# SparkFun_ESP32_Power_Control_Shield.net
KiCad netlist of a schematic drawn in EAGLE
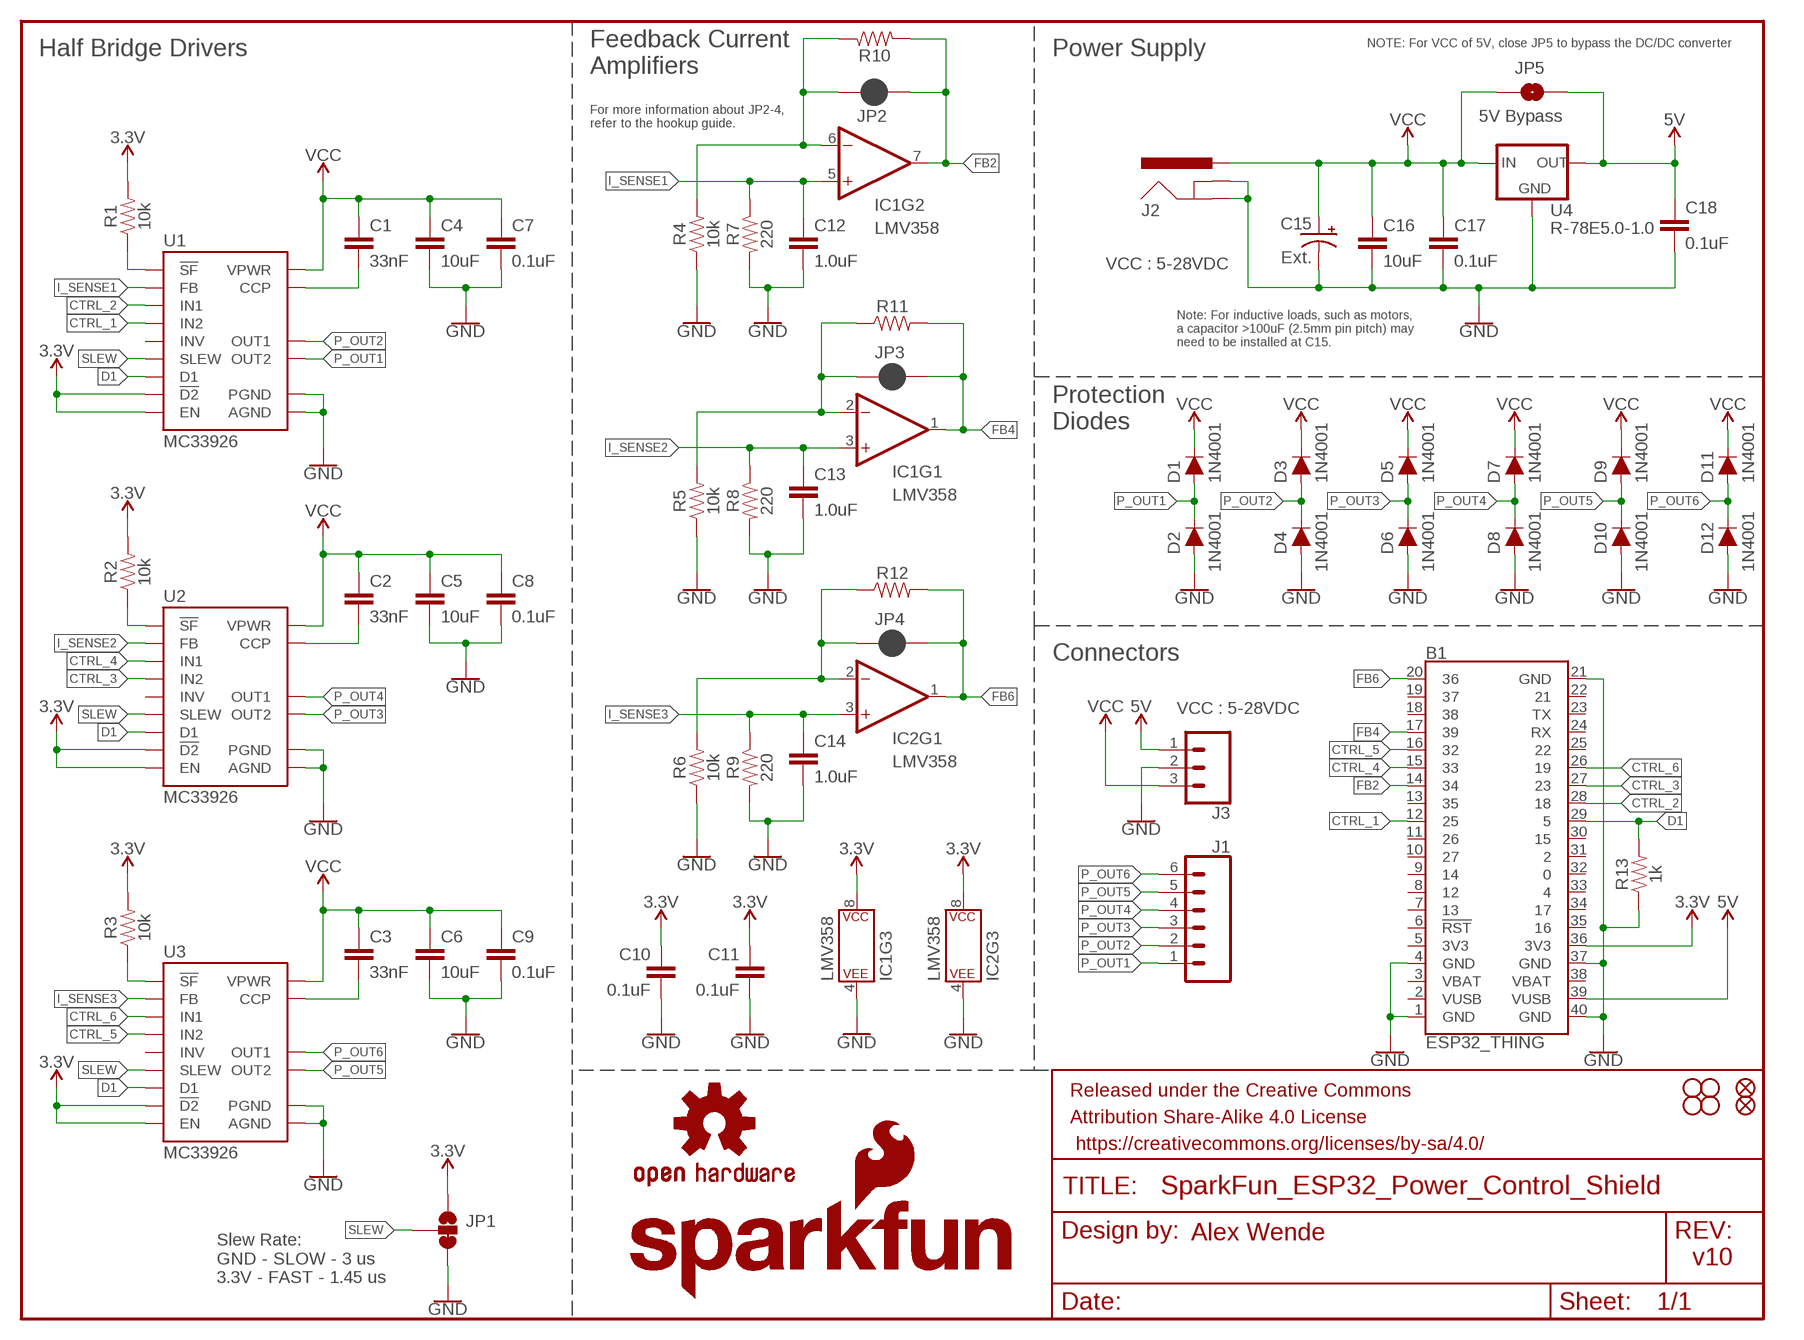
[diagram p0: schematic, sheet 1]

(export (version "E")
  (design (tool "Eeschema 10.0.6"))
  (components
    (comp (ref "B1")
      (value "ESP32_THING")
      (footprint "eagle-import:ESP32_THING")
      (libsource (lib "eagle-import") (part "ESP32_THING"))
    )
    (comp (ref "C1")
      (value "33nF")
      (footprint "eagle-import:0603")
      (libsource (lib "eagle-import") (part "33NF-0603-50V-10%"))
    )
    (comp (ref "C2")
      (value "33nF")
      (footprint "eagle-import:0603")
      (libsource (lib "eagle-import") (part "33NF-0603-50V-10%"))
    )
    (comp (ref "C3")
      (value "33nF")
      (footprint "eagle-import:0603")
      (libsource (lib "eagle-import") (part "33NF-0603-50V-10%"))
    )
    (comp (ref "C4")
      (value "10uF")
      (footprint "eagle-import:1210")
      (libsource (lib "eagle-import") (part "10UF-1210-50V-20%"))
    )
    (comp (ref "C5")
      (value "10uF")
      (footprint "eagle-import:1210")
      (libsource (lib "eagle-import") (part "10UF-1210-50V-20%"))
    )
    (comp (ref "C6")
      (value "10uF")
      (footprint "eagle-import:1210")
      (libsource (lib "eagle-import") (part "10UF-1210-50V-20%"))
    )
    (comp (ref "C7")
      (value "0.1uF")
      (footprint "eagle-import:0603")
      (libsource (lib "eagle-import") (part "0.1UF-0603-100V-10%"))
    )
    (comp (ref "C8")
      (value "0.1uF")
      (footprint "eagle-import:0603")
      (libsource (lib "eagle-import") (part "0.1UF-0603-100V-10%"))
    )
    (comp (ref "C9")
      (value "0.1uF")
      (footprint "eagle-import:0603")
      (libsource (lib "eagle-import") (part "0.1UF-0603-100V-10%"))
    )
    (comp (ref "C10")
      (value "0.1uF")
      (footprint "eagle-import:0603")
      (libsource (lib "eagle-import") (part "0.1UF-0603-100V-10%"))
    )
    (comp (ref "C11")
      (value "0.1uF")
      (footprint "eagle-import:0603")
      (libsource (lib "eagle-import") (part "0.1UF-0603-100V-10%"))
    )
    (comp (ref "C12")
      (value "1.0uF")
      (footprint "eagle-import:0603")
      (libsource (lib "eagle-import") (part "1.0UF-0603-16V-10%"))
    )
    (comp (ref "C13")
      (value "1.0uF")
      (footprint "eagle-import:0603")
      (libsource (lib "eagle-import") (part "1.0UF-0603-16V-10%"))
    )
    (comp (ref "C14")
      (value "1.0uF")
      (footprint "eagle-import:0603")
      (libsource (lib "eagle-import") (part "1.0UF-0603-16V-10%"))
    )
    (comp (ref "C15")
      (value "Ext.")
      (footprint "eagle-import:CPOL-RADIAL-2.5MM-6.5MM")
      (libsource (lib "eagle-import") (part "100UF-POLAR-RADIAL-2.5MM-25V-20%"))
    )
    (comp (ref "C16")
      (value "10uF")
      (footprint "eagle-import:1210")
      (libsource (lib "eagle-import") (part "10UF-1210-50V-20%"))
    )
    (comp (ref "C17")
      (value "0.1uF")
      (footprint "eagle-import:0603")
      (libsource (lib "eagle-import") (part "0.1UF-0603-100V-10%"))
    )
    (comp (ref "C18")
      (value "0.1uF")
      (footprint "eagle-import:0603")
      (libsource (lib "eagle-import") (part "0.1UF-0603-100V-10%"))
    )
    (comp (ref "D1")
      (value "1N4001")
      (footprint "eagle-import:DIODE-1N4001")
      (libsource (lib "eagle-import") (part "DIODE-PTH"))
    )
    (comp (ref "D2")
      (value "1N4001")
      (footprint "eagle-import:DIODE-1N4001")
      (libsource (lib "eagle-import") (part "DIODE-PTH"))
    )
    (comp (ref "D3")
      (value "1N4001")
      (footprint "eagle-import:DIODE-1N4001")
      (libsource (lib "eagle-import") (part "DIODE-PTH"))
    )
    (comp (ref "D4")
      (value "1N4001")
      (footprint "eagle-import:DIODE-1N4001")
      (libsource (lib "eagle-import") (part "DIODE-PTH"))
    )
    (comp (ref "D5")
      (value "1N4001")
      (footprint "eagle-import:DIODE-1N4001")
      (libsource (lib "eagle-import") (part "DIODE-PTH"))
    )
    (comp (ref "D6")
      (value "1N4001")
      (footprint "eagle-import:DIODE-1N4001")
      (libsource (lib "eagle-import") (part "DIODE-PTH"))
    )
    (comp (ref "D7")
      (value "1N4001")
      (footprint "eagle-import:DIODE-1N4001")
      (libsource (lib "eagle-import") (part "DIODE-PTH"))
    )
    (comp (ref "D8")
      (value "1N4001")
      (footprint "eagle-import:DIODE-1N4001")
      (libsource (lib "eagle-import") (part "DIODE-PTH"))
    )
    (comp (ref "D9")
      (value "1N4001")
      (footprint "eagle-import:DIODE-1N4001")
      (libsource (lib "eagle-import") (part "DIODE-PTH"))
    )
    (comp (ref "D10")
      (value "1N4001")
      (footprint "eagle-import:DIODE-1N4001")
      (libsource (lib "eagle-import") (part "DIODE-PTH"))
    )
    (comp (ref "D11")
      (value "1N4001")
      (footprint "eagle-import:DIODE-1N4001")
      (libsource (lib "eagle-import") (part "DIODE-PTH"))
    )
    (comp (ref "D12")
      (value "1N4001")
      (footprint "eagle-import:DIODE-1N4001")
      (libsource (lib "eagle-import") (part "DIODE-PTH"))
    )
    (comp (ref "FD1")
      (value "FIDUCIALUFIDUCIAL")
      (footprint "eagle-import:FIDUCIAL-MICRO")
      (libsource (lib "eagle-import") (part "FIDUCIALUFIDUCIAL"))
    )
    (comp (ref "FD2")
      (value "FIDUCIALUFIDUCIAL")
      (footprint "eagle-import:FIDUCIAL-MICRO")
      (libsource (lib "eagle-import") (part "FIDUCIALUFIDUCIAL"))
    )
    (comp (ref "FRAME1")
      (value "FRAME-LETTER")
      (footprint "eagle-import:CREATIVE_COMMONS")
      (libsource (lib "eagle-import") (part "FRAME-LETTER"))
    )
    (comp (ref "H1")
      (value "STAND-OFF")
      (footprint "eagle-import:STAND-OFF")
      (libsource (lib "eagle-import") (part "STAND-OFF"))
    )
    (comp (ref "H2")
      (value "STAND-OFF")
      (footprint "eagle-import:STAND-OFF")
      (libsource (lib "eagle-import") (part "STAND-OFF"))
    )
    (comp (ref "H3")
      (value "STAND-OFF")
      (footprint "eagle-import:STAND-OFF")
      (libsource (lib "eagle-import") (part "STAND-OFF"))
    )
    (comp (ref "H4")
      (value "STAND-OFF")
      (footprint "eagle-import:STAND-OFF")
      (libsource (lib "eagle-import") (part "STAND-OFF"))
    )
    (comp (ref "IC1")
      (value "LMV358")
      (footprint "eagle-import:SO08")
      (libsource (lib "eagle-import") (part "OPAMP-DUALU"))
    )
    (comp (ref "IC2")
      (value "LMV358")
      (footprint "eagle-import:SO08")
      (libsource (lib "eagle-import") (part "OPAMP-DUALU"))
    )
    (comp (ref "J1")
      (value "CONN_063.5MM-6")
      (footprint "eagle-import:SCREWTERMINAL-3.5MM-6")
      (libsource (lib "eagle-import") (part "CONN_063.5MM-6"))
    )
    (comp (ref "J2")
      (value "POWER_JACKPTH_LOCK")
      (footprint "eagle-import:POWER_JACK_PTH_LOCK")
      (libsource (lib "eagle-import") (part "POWER_JACKPTH_LOCK"))
    )
    (comp (ref "J3")
      (value "CONN_03SCREW")
      (footprint "eagle-import:SCREWTERMINAL-3.5MM-3")
      (libsource (lib "eagle-import") (part "CONN_03SCREW"))
    )
    (comp (ref "JP1")
      (value "JUMPER-SMT_3_1-NC_TRACE_SILK")
      (footprint "eagle-import:SMT-JUMPER_3_1-NC_TRACE_SILK")
      (libsource (lib "eagle-import") (part "JUMPER-SMT_3_1-NC_TRACE_SILK"))
    )
    (comp (ref "JP2")
      (value "JUMPER-SMT_2_NC_PASTE_NO-SILK")
      (footprint "eagle-import:SMT-JUMPER_2_NC_PASTE_NO-SILK")
      (libsource (lib "eagle-import") (part "JUMPER-SMT_2_NC_PASTE_NO-SILK"))
    )
    (comp (ref "JP3")
      (value "JUMPER-SMT_2_NC_PASTE_NO-SILK")
      (footprint "eagle-import:SMT-JUMPER_2_NC_PASTE_NO-SILK")
      (libsource (lib "eagle-import") (part "JUMPER-SMT_2_NC_PASTE_NO-SILK"))
    )
    (comp (ref "JP4")
      (value "JUMPER-SMT_2_NC_PASTE_NO-SILK")
      (footprint "eagle-import:SMT-JUMPER_2_NC_PASTE_NO-SILK")
      (libsource (lib "eagle-import") (part "JUMPER-SMT_2_NC_PASTE_NO-SILK"))
    )
    (comp (ref "JP5")
      (value "5V Bypass")
      (footprint "eagle-import:SMT-JUMPER_2_NO_SILK")
      (libsource (lib "eagle-import") (part "JUMPER-SMT_2_NO_SILK"))
    )
    (comp (ref "LOGO1")
      (value "SFE_LOGO_NAME_FLAME.2_INCH")
      (footprint "eagle-import:SFE_LOGO_NAME_FLAME_.2")
      (libsource (lib "eagle-import") (part "SFE_LOGO_NAME_FLAME.2_INCH"))
    )
    (comp (ref "LOGO2")
      (value "OSHW-LOGOM")
      (footprint "eagle-import:OSHW-LOGO-M")
      (libsource (lib "eagle-import") (part "OSHW-LOGOM"))
    )
    (comp (ref "R1")
      (value "10k")
      (footprint "eagle-import:0603")
      (libsource (lib "eagle-import") (part "10KOHM-0603-1/10W-1%"))
    )
    (comp (ref "R2")
      (value "10k")
      (footprint "eagle-import:0603")
      (libsource (lib "eagle-import") (part "10KOHM-0603-1/10W-1%"))
    )
    (comp (ref "R3")
      (value "10k")
      (footprint "eagle-import:0603")
      (libsource (lib "eagle-import") (part "10KOHM-0603-1/10W-1%"))
    )
    (comp (ref "R4")
      (value "10k")
      (footprint "eagle-import:0603")
      (libsource (lib "eagle-import") (part "10KOHM-0603-1/10W-1%"))
    )
    (comp (ref "R5")
      (value "10k")
      (footprint "eagle-import:0603")
      (libsource (lib "eagle-import") (part "10KOHM-0603-1/10W-1%"))
    )
    (comp (ref "R6")
      (value "10k")
      (footprint "eagle-import:0603")
      (libsource (lib "eagle-import") (part "10KOHM-0603-1/10W-1%"))
    )
    (comp (ref "R7")
      (value "220")
      (footprint "eagle-import:0603")
      (libsource (lib "eagle-import") (part "220OHM-0603-1/10W-1%"))
    )
    (comp (ref "R8")
      (value "220")
      (footprint "eagle-import:0603")
      (libsource (lib "eagle-import") (part "220OHM-0603-1/10W-1%"))
    )
    (comp (ref "R9")
      (value "220")
      (footprint "eagle-import:0603")
      (libsource (lib "eagle-import") (part "220OHM-0603-1/10W-1%"))
    )
    (comp (ref "R10")
      (value "1KOHM-HORIZ-1/4W-1%")
      (footprint "eagle-import:AXIAL-0.3")
      (libsource (lib "eagle-import") (part "1KOHM-HORIZ-1/4W-1%"))
    )
    (comp (ref "R11")
      (value "1KOHM-HORIZ-1/4W-1%")
      (footprint "eagle-import:AXIAL-0.3")
      (libsource (lib "eagle-import") (part "1KOHM-HORIZ-1/4W-1%"))
    )
    (comp (ref "R12")
      (value "1KOHM-HORIZ-1/4W-1%")
      (footprint "eagle-import:AXIAL-0.3")
      (libsource (lib "eagle-import") (part "1KOHM-HORIZ-1/4W-1%"))
    )
    (comp (ref "R13")
      (value "1k")
      (footprint "eagle-import:0603")
      (libsource (lib "eagle-import") (part "1KOHM-0603-1/10W-1%"))
    )
    (comp (ref "U1")
      (value "MC33926")
      (footprint "eagle-import:32-PQFN")
      (libsource (lib "eagle-import") (part "MC33926"))
    )
    (comp (ref "U2")
      (value "MC33926")
      (footprint "eagle-import:32-PQFN")
      (libsource (lib "eagle-import") (part "MC33926"))
    )
    (comp (ref "U3")
      (value "MC33926")
      (footprint "eagle-import:32-PQFN")
      (libsource (lib "eagle-import") (part "MC33926"))
    )
    (comp (ref "U4")
      (value "R-78E5.0-1.0")
      (footprint "eagle-import:DC-DC_CONVERTER_78XX")
      (libsource (lib "eagle-import") (part "R-78E5.0-1.0"))
    )
  )
  (nets
    (net (code "1") (name "3.3V") (class "Default")
      (node (ref "B1") (pin "36") (pinfunction "3V3_36") (pintype "bidirectional"))
      (node (ref "C10") (pin "1") (pinfunction "1_1") (pintype "passive"))
      (node (ref "C11") (pin "1") (pinfunction "1_1") (pintype "passive"))
      (node (ref "IC1") (pin "8") (pinfunction "P$V+_8") (pintype "bidirectional"))
      (node (ref "IC2") (pin "8") (pinfunction "P$V+_8") (pintype "bidirectional"))
      (node (ref "JP1") (pin "1") (pinfunction "1_1") (pintype "passive"))
      (node (ref "R1") (pin "2") (pinfunction "2_2") (pintype "passive"))
      (node (ref "R2") (pin "2") (pinfunction "2_2") (pintype "passive"))
      (node (ref "R3") (pin "2") (pinfunction "2_2") (pintype "passive"))
      (node (ref "U1") (pin "P$10") (pinfunction "EN_P$10") (pintype "bidirectional"))
      (node (ref "U1") (pin "P$16") (pinfunction "~{D2}_P$16") (pintype "bidirectional"))
      (node (ref "U2") (pin "P$10") (pinfunction "EN_P$10") (pintype "bidirectional"))
      (node (ref "U2") (pin "P$16") (pinfunction "~{D2}_P$16") (pintype "bidirectional"))
      (node (ref "U3") (pin "P$10") (pinfunction "EN_P$10") (pintype "bidirectional"))
      (node (ref "U3") (pin "P$16") (pinfunction "~{D2}_P$16") (pintype "bidirectional"))
    )
    (net (code "2") (name "5V") (class "Default")
      (node (ref "B1") (pin "39") (pinfunction "VUSB_39") (pintype "bidirectional"))
      (node (ref "C18") (pin "1") (pinfunction "1_1") (pintype "passive"))
      (node (ref "J3") (pin "1") (pinfunction "1_1") (pintype "passive"))
      (node (ref "JP5") (pin "2") (pinfunction "2_2") (pintype "passive"))
      (node (ref "U4") (pin "VOUT") (pinfunction "OUT_VOUT") (pintype "passive"))
    )
    (net (code "3") (name "CTRL_1") (class "Default")
      (node (ref "B1") (pin "12") (pinfunction "25_12") (pintype "bidirectional"))
      (node (ref "U1") (pin "P$1") (pinfunction "IN2_P$1") (pintype "bidirectional"))
    )
    (net (code "4") (name "CTRL_2") (class "Default")
      (node (ref "B1") (pin "28") (pinfunction "18_28") (pintype "bidirectional"))
      (node (ref "U1") (pin "P$2") (pinfunction "IN1_P$2") (pintype "bidirectional"))
    )
    (net (code "5") (name "CTRL_3") (class "Default")
      (node (ref "B1") (pin "27") (pinfunction "23_27") (pintype "bidirectional"))
      (node (ref "U2") (pin "P$1") (pinfunction "IN2_P$1") (pintype "bidirectional"))
    )
    (net (code "6") (name "CTRL_4") (class "Default")
      (node (ref "B1") (pin "15") (pinfunction "33_15") (pintype "bidirectional"))
      (node (ref "U2") (pin "P$2") (pinfunction "IN1_P$2") (pintype "bidirectional"))
    )
    (net (code "7") (name "CTRL_5") (class "Default")
      (node (ref "B1") (pin "16") (pinfunction "32_16") (pintype "bidirectional"))
      (node (ref "U3") (pin "P$1") (pinfunction "IN2_P$1") (pintype "bidirectional"))
    )
    (net (code "8") (name "CTRL_6") (class "Default")
      (node (ref "B1") (pin "26") (pinfunction "19_26") (pintype "bidirectional"))
      (node (ref "U3") (pin "P$2") (pinfunction "IN1_P$2") (pintype "bidirectional"))
    )
    (net (code "9") (name "D1") (class "Default")
      (node (ref "B1") (pin "29") (pinfunction "5_29") (pintype "bidirectional"))
      (node (ref "R13") (pin "2") (pinfunction "2_2") (pintype "passive"))
      (node (ref "U1") (pin "P$26") (pinfunction "D1_P$26") (pintype "bidirectional"))
      (node (ref "U2") (pin "P$26") (pinfunction "D1_P$26") (pintype "bidirectional"))
      (node (ref "U3") (pin "P$26") (pinfunction "D1_P$26") (pintype "bidirectional"))
    )
    (net (code "10") (name "FB2") (class "Default")
      (node (ref "B1") (pin "14") (pinfunction "34_14") (pintype "bidirectional"))
      (node (ref "IC1") (pin "7") (pinfunction "OUT_7") (pintype "output"))
      (node (ref "JP2") (pin "2") (pinfunction "2_2") (pintype "passive"))
      (node (ref "R10") (pin "P$2") (pinfunction "2_P$2") (pintype "passive"))
    )
    (net (code "11") (name "FB4") (class "Default")
      (node (ref "B1") (pin "17") (pinfunction "39_17") (pintype "bidirectional"))
      (node (ref "IC1") (pin "1") (pinfunction "OUT_1") (pintype "output"))
      (node (ref "JP3") (pin "2") (pinfunction "2_2") (pintype "passive"))
      (node (ref "R11") (pin "P$2") (pinfunction "2_P$2") (pintype "passive"))
    )
    (net (code "12") (name "FB6") (class "Default")
      (node (ref "B1") (pin "20") (pinfunction "36_20") (pintype "bidirectional"))
      (node (ref "IC2") (pin "1") (pinfunction "OUT_1") (pintype "output"))
      (node (ref "JP4") (pin "2") (pinfunction "2_2") (pintype "passive"))
      (node (ref "R12") (pin "P$2") (pinfunction "2_P$2") (pintype "passive"))
    )
    (net (code "13") (name "GND") (class "Default")
      (node (ref "B1") (pin "1") (pinfunction "GND_1") (pintype "bidirectional"))
      (node (ref "B1") (pin "21") (pinfunction "GND_21") (pintype "bidirectional"))
      (node (ref "B1") (pin "37") (pinfunction "GND_37") (pintype "bidirectional"))
      (node (ref "B1") (pin "4") (pinfunction "GND_4") (pintype "bidirectional"))
      (node (ref "B1") (pin "40") (pinfunction "GND_40") (pintype "bidirectional"))
      (node (ref "C10") (pin "2") (pinfunction "2_2") (pintype "passive"))
      (node (ref "C11") (pin "2") (pinfunction "2_2") (pintype "passive"))
      (node (ref "C12") (pin "2") (pinfunction "2_2") (pintype "passive"))
      (node (ref "C13") (pin "2") (pinfunction "2_2") (pintype "passive"))
      (node (ref "C14") (pin "2") (pinfunction "2_2") (pintype "passive"))
      (node (ref "C15") (pin "2") (pinfunction "-_2") (pintype "passive"))
      (node (ref "C16") (pin "2") (pinfunction "2_2") (pintype "passive"))
      (node (ref "C17") (pin "2") (pinfunction "2_2") (pintype "passive"))
      (node (ref "C18") (pin "2") (pinfunction "2_2") (pintype "passive"))
      (node (ref "C4") (pin "2") (pinfunction "2_2") (pintype "passive"))
      (node (ref "C5") (pin "2") (pinfunction "2_2") (pintype "passive"))
      (node (ref "C6") (pin "2") (pinfunction "2_2") (pintype "passive"))
      (node (ref "C7") (pin "2") (pinfunction "2_2") (pintype "passive"))
      (node (ref "C8") (pin "2") (pinfunction "2_2") (pintype "passive"))
      (node (ref "C9") (pin "2") (pinfunction "2_2") (pintype "passive"))
      (node (ref "D10") (pin "A") (pinfunction "A_A") (pintype "passive"))
      (node (ref "D12") (pin "A") (pinfunction "A_A") (pintype "passive"))
      (node (ref "D2") (pin "A") (pinfunction "A_A") (pintype "passive"))
      (node (ref "D4") (pin "A") (pinfunction "A_A") (pintype "passive"))
      (node (ref "D6") (pin "A") (pinfunction "A_A") (pintype "passive"))
      (node (ref "D8") (pin "A") (pinfunction "A_A") (pintype "passive"))
      (node (ref "IC1") (pin "4") (pinfunction "P$V-_4") (pintype "bidirectional"))
      (node (ref "IC2") (pin "4") (pinfunction "P$V-_4") (pintype "bidirectional"))
      (node (ref "J2") (pin "GND") (pinfunction "GND_GND") (pintype "bidirectional"))
      (node (ref "J2") (pin "GNDBREAK") (pinfunction "GNDBREAK_GNDBREAK") (pintype "bidirectional"))
      (node (ref "J3") (pin "2") (pinfunction "2_2") (pintype "passive"))
      (node (ref "JP1") (pin "3") (pinfunction "3_3") (pintype "passive"))
      (node (ref "R13") (pin "1") (pinfunction "1_1") (pintype "passive"))
      (node (ref "R4") (pin "1") (pinfunction "1_1") (pintype "passive"))
      (node (ref "R5") (pin "1") (pinfunction "1_1") (pintype "passive"))
      (node (ref "R6") (pin "1") (pinfunction "1_1") (pintype "passive"))
      (node (ref "R7") (pin "2") (pinfunction "2_2") (pintype "passive"))
      (node (ref "R8") (pin "2") (pinfunction "2_2") (pintype "passive"))
      (node (ref "R9") (pin "2") (pinfunction "2_2") (pintype "passive"))
      (node (ref "U1") (pin "P$18") (pinfunction "PGND_P$18") (pintype "bidirectional"))
      (node (ref "U1") (pin "P$19") (pinfunction "PGND_P$19") (pintype "bidirectional"))
      (node (ref "U1") (pin "P$20") (pinfunction "PGND_P$20") (pintype "bidirectional"))
      (node (ref "U1") (pin "P$22") (pinfunction "PGND_P$22") (pintype "bidirectional"))
      (node (ref "U1") (pin "P$23") (pinfunction "PGND_P$23") (pintype "bidirectional"))
      (node (ref "U1") (pin "P$24") (pinfunction "PGND_P$24") (pintype "bidirectional"))
      (node (ref "U1") (pin "P$33") (pinfunction "AGND_P$33") (pintype "bidirectional"))
      (node (ref "U1") (pin "P$5") (pinfunction "AGND_P$5") (pintype "bidirectional"))
      (node (ref "U2") (pin "P$18") (pinfunction "PGND_P$18") (pintype "bidirectional"))
      (node (ref "U2") (pin "P$19") (pinfunction "PGND_P$19") (pintype "bidirectional"))
      (node (ref "U2") (pin "P$20") (pinfunction "PGND_P$20") (pintype "bidirectional"))
      (node (ref "U2") (pin "P$22") (pinfunction "PGND_P$22") (pintype "bidirectional"))
      (node (ref "U2") (pin "P$23") (pinfunction "PGND_P$23") (pintype "bidirectional"))
      (node (ref "U2") (pin "P$24") (pinfunction "PGND_P$24") (pintype "bidirectional"))
      (node (ref "U2") (pin "P$33") (pinfunction "AGND_P$33") (pintype "bidirectional"))
      (node (ref "U2") (pin "P$5") (pinfunction "AGND_P$5") (pintype "bidirectional"))
      (node (ref "U3") (pin "P$18") (pinfunction "PGND_P$18") (pintype "bidirectional"))
      (node (ref "U3") (pin "P$19") (pinfunction "PGND_P$19") (pintype "bidirectional"))
      (node (ref "U3") (pin "P$20") (pinfunction "PGND_P$20") (pintype "bidirectional"))
      (node (ref "U3") (pin "P$22") (pinfunction "PGND_P$22") (pintype "bidirectional"))
      (node (ref "U3") (pin "P$23") (pinfunction "PGND_P$23") (pintype "bidirectional"))
      (node (ref "U3") (pin "P$24") (pinfunction "PGND_P$24") (pintype "bidirectional"))
      (node (ref "U3") (pin "P$33") (pinfunction "AGND_P$33") (pintype "bidirectional"))
      (node (ref "U3") (pin "P$5") (pinfunction "AGND_P$5") (pintype "bidirectional"))
      (node (ref "U4") (pin "GND") (pinfunction "GND_GND") (pintype "input"))
    )
    (net (code "14") (name "I_SENSE1") (class "Default")
      (node (ref "C12") (pin "1") (pinfunction "1_1") (pintype "passive"))
      (node (ref "IC1") (pin "5") (pinfunction "+IN_5") (pintype "input"))
      (node (ref "R7") (pin "1") (pinfunction "1_1") (pintype "passive"))
      (node (ref "U1") (pin "P$8") (pinfunction "FB_P$8") (pintype "bidirectional"))
    )
    (net (code "15") (name "I_SENSE2") (class "Default")
      (node (ref "C13") (pin "1") (pinfunction "1_1") (pintype "passive"))
      (node (ref "IC1") (pin "3") (pinfunction "+IN_3") (pintype "input"))
      (node (ref "R8") (pin "1") (pinfunction "1_1") (pintype "passive"))
      (node (ref "U2") (pin "P$8") (pinfunction "FB_P$8") (pintype "bidirectional"))
    )
    (net (code "16") (name "I_SENSE3") (class "Default")
      (node (ref "C14") (pin "1") (pinfunction "1_1") (pintype "passive"))
      (node (ref "IC2") (pin "3") (pinfunction "+IN_3") (pintype "input"))
      (node (ref "R9") (pin "1") (pinfunction "1_1") (pintype "passive"))
      (node (ref "U3") (pin "P$8") (pinfunction "FB_P$8") (pintype "bidirectional"))
    )
    (net (code "17") (name "Net-(IC1A--IN)") (class "Default")
      (node (ref "IC1") (pin "2") (pinfunction "-IN_2") (pintype "input"))
      (node (ref "JP3") (pin "1") (pinfunction "1_1") (pintype "passive"))
      (node (ref "R11") (pin "P$1") (pinfunction "1_P$1") (pintype "passive"))
      (node (ref "R5") (pin "2") (pinfunction "2_2") (pintype "passive"))
    )
    (net (code "18") (name "Net-(IC1B--IN)") (class "Default")
      (node (ref "IC1") (pin "6") (pinfunction "-IN_6") (pintype "input"))
      (node (ref "JP2") (pin "1") (pinfunction "1_1") (pintype "passive"))
      (node (ref "R10") (pin "P$1") (pinfunction "1_P$1") (pintype "passive"))
      (node (ref "R4") (pin "2") (pinfunction "2_2") (pintype "passive"))
    )
    (net (code "19") (name "Net-(IC2A--IN)") (class "Default")
      (node (ref "IC2") (pin "2") (pinfunction "-IN_2") (pintype "input"))
      (node (ref "JP4") (pin "1") (pinfunction "1_1") (pintype "passive"))
      (node (ref "R12") (pin "P$1") (pinfunction "1_P$1") (pintype "passive"))
      (node (ref "R6") (pin "2") (pinfunction "2_2") (pintype "passive"))
    )
    (net (code "20") (name "Net-(U1-CCP)") (class "Default")
      (node (ref "C1") (pin "2") (pinfunction "2_2") (pintype "passive"))
      (node (ref "U1") (pin "P$32") (pinfunction "CCP_P$32") (pintype "bidirectional"))
    )
    (net (code "21") (name "Net-(U1-~{SF})") (class "Default")
      (node (ref "R1") (pin "1") (pinfunction "1_1") (pintype "passive"))
      (node (ref "U1") (pin "P$21") (pinfunction "~{SF}_P$21") (pintype "bidirectional"))
    )
    (net (code "22") (name "Net-(U2-CCP)") (class "Default")
      (node (ref "C2") (pin "2") (pinfunction "2_2") (pintype "passive"))
      (node (ref "U2") (pin "P$32") (pinfunction "CCP_P$32") (pintype "bidirectional"))
    )
    (net (code "23") (name "Net-(U2-~{SF})") (class "Default")
      (node (ref "R2") (pin "1") (pinfunction "1_1") (pintype "passive"))
      (node (ref "U2") (pin "P$21") (pinfunction "~{SF}_P$21") (pintype "bidirectional"))
    )
    (net (code "24") (name "Net-(U3-CCP)") (class "Default")
      (node (ref "C3") (pin "2") (pinfunction "2_2") (pintype "passive"))
      (node (ref "U3") (pin "P$32") (pinfunction "CCP_P$32") (pintype "bidirectional"))
    )
    (net (code "25") (name "Net-(U3-~{SF})") (class "Default")
      (node (ref "R3") (pin "1") (pinfunction "1_1") (pintype "passive"))
      (node (ref "U3") (pin "P$21") (pinfunction "~{SF}_P$21") (pintype "bidirectional"))
    )
    (net (code "26") (name "P_OUT1") (class "Default")
      (node (ref "D1") (pin "A") (pinfunction "A_A") (pintype "passive"))
      (node (ref "D2") (pin "C") (pinfunction "C_C") (pintype "passive"))
      (node (ref "J1") (pin "1") (pinfunction "1_1") (pintype "passive"))
      (node (ref "U1") (pin "P$27") (pinfunction "OUT2_P$27") (pintype "bidirectional"))
      (node (ref "U1") (pin "P$28") (pinfunction "OUT2_P$28") (pintype "bidirectional"))
      (node (ref "U1") (pin "P$29") (pinfunction "OUT2_P$29") (pintype "bidirectional"))
      (node (ref "U1") (pin "P$30") (pinfunction "OUT2_P$30") (pintype "bidirectional"))
    )
    (net (code "27") (name "P_OUT2") (class "Default")
      (node (ref "D3") (pin "A") (pinfunction "A_A") (pintype "passive"))
      (node (ref "D4") (pin "C") (pinfunction "C_C") (pintype "passive"))
      (node (ref "J1") (pin "2") (pinfunction "2_2") (pintype "passive"))
      (node (ref "U1") (pin "P$12") (pinfunction "OUT1_P$12") (pintype "bidirectional"))
      (node (ref "U1") (pin "P$13") (pinfunction "OUT1_P$13") (pintype "bidirectional"))
      (node (ref "U1") (pin "P$14") (pinfunction "OUT1_P$14") (pintype "bidirectional"))
      (node (ref "U1") (pin "P$15") (pinfunction "OUT1_P$15") (pintype "bidirectional"))
    )
    (net (code "28") (name "P_OUT3") (class "Default")
      (node (ref "D5") (pin "A") (pinfunction "A_A") (pintype "passive"))
      (node (ref "D6") (pin "C") (pinfunction "C_C") (pintype "passive"))
      (node (ref "J1") (pin "3") (pinfunction "3_3") (pintype "passive"))
      (node (ref "U2") (pin "P$27") (pinfunction "OUT2_P$27") (pintype "bidirectional"))
      (node (ref "U2") (pin "P$28") (pinfunction "OUT2_P$28") (pintype "bidirectional"))
      (node (ref "U2") (pin "P$29") (pinfunction "OUT2_P$29") (pintype "bidirectional"))
      (node (ref "U2") (pin "P$30") (pinfunction "OUT2_P$30") (pintype "bidirectional"))
    )
    (net (code "29") (name "P_OUT4") (class "Default")
      (node (ref "D7") (pin "A") (pinfunction "A_A") (pintype "passive"))
      (node (ref "D8") (pin "C") (pinfunction "C_C") (pintype "passive"))
      (node (ref "J1") (pin "4") (pinfunction "4_4") (pintype "passive"))
      (node (ref "U2") (pin "P$12") (pinfunction "OUT1_P$12") (pintype "bidirectional"))
      (node (ref "U2") (pin "P$13") (pinfunction "OUT1_P$13") (pintype "bidirectional"))
      (node (ref "U2") (pin "P$14") (pinfunction "OUT1_P$14") (pintype "bidirectional"))
      (node (ref "U2") (pin "P$15") (pinfunction "OUT1_P$15") (pintype "bidirectional"))
    )
    (net (code "30") (name "P_OUT5") (class "Default")
      (node (ref "D10") (pin "C") (pinfunction "C_C") (pintype "passive"))
      (node (ref "D9") (pin "A") (pinfunction "A_A") (pintype "passive"))
      (node (ref "J1") (pin "5") (pinfunction "5_5") (pintype "passive"))
      (node (ref "U3") (pin "P$27") (pinfunction "OUT2_P$27") (pintype "bidirectional"))
      (node (ref "U3") (pin "P$28") (pinfunction "OUT2_P$28") (pintype "bidirectional"))
      (node (ref "U3") (pin "P$29") (pinfunction "OUT2_P$29") (pintype "bidirectional"))
      (node (ref "U3") (pin "P$30") (pinfunction "OUT2_P$30") (pintype "bidirectional"))
    )
    (net (code "31") (name "P_OUT6") (class "Default")
      (node (ref "D11") (pin "A") (pinfunction "A_A") (pintype "passive"))
      (node (ref "D12") (pin "C") (pinfunction "C_C") (pintype "passive"))
      (node (ref "J1") (pin "6") (pinfunction "6_6") (pintype "passive"))
      (node (ref "U3") (pin "P$12") (pinfunction "OUT1_P$12") (pintype "bidirectional"))
      (node (ref "U3") (pin "P$13") (pinfunction "OUT1_P$13") (pintype "bidirectional"))
      (node (ref "U3") (pin "P$14") (pinfunction "OUT1_P$14") (pintype "bidirectional"))
      (node (ref "U3") (pin "P$15") (pinfunction "OUT1_P$15") (pintype "bidirectional"))
    )
    (net (code "32") (name "SLEW") (class "Default")
      (node (ref "JP1") (pin "2") (pinfunction "2_2") (pintype "passive"))
      (node (ref "U1") (pin "P$3") (pinfunction "SLEW_P$3") (pintype "bidirectional"))
      (node (ref "U2") (pin "P$3") (pinfunction "SLEW_P$3") (pintype "bidirectional"))
      (node (ref "U3") (pin "P$3") (pinfunction "SLEW_P$3") (pintype "bidirectional"))
    )
    (net (code "33") (name "VCC") (class "Default")
      (node (ref "C1") (pin "1") (pinfunction "1_1") (pintype "passive"))
      (node (ref "C15") (pin "1") (pinfunction "+_1") (pintype "passive"))
      (node (ref "C16") (pin "1") (pinfunction "1_1") (pintype "passive"))
      (node (ref "C17") (pin "1") (pinfunction "1_1") (pintype "passive"))
      (node (ref "C2") (pin "1") (pinfunction "1_1") (pintype "passive"))
      (node (ref "C3") (pin "1") (pinfunction "1_1") (pintype "passive"))
      (node (ref "C4") (pin "1") (pinfunction "1_1") (pintype "passive"))
      (node (ref "C5") (pin "1") (pinfunction "1_1") (pintype "passive"))
      (node (ref "C6") (pin "1") (pinfunction "1_1") (pintype "passive"))
      (node (ref "C7") (pin "1") (pinfunction "1_1") (pintype "passive"))
      (node (ref "C8") (pin "1") (pinfunction "1_1") (pintype "passive"))
      (node (ref "C9") (pin "1") (pinfunction "1_1") (pintype "passive"))
      (node (ref "D1") (pin "C") (pinfunction "C_C") (pintype "passive"))
      (node (ref "D11") (pin "C") (pinfunction "C_C") (pintype "passive"))
      (node (ref "D3") (pin "C") (pinfunction "C_C") (pintype "passive"))
      (node (ref "D5") (pin "C") (pinfunction "C_C") (pintype "passive"))
      (node (ref "D7") (pin "C") (pinfunction "C_C") (pintype "passive"))
      (node (ref "D9") (pin "C") (pinfunction "C_C") (pintype "passive"))
      (node (ref "J2") (pin "PWR") (pinfunction "PWR_PWR") (pintype "bidirectional"))
      (node (ref "J3") (pin "3") (pinfunction "3_3") (pintype "passive"))
      (node (ref "JP5") (pin "1") (pinfunction "1_1") (pintype "passive"))
      (node (ref "U1") (pin "P$11") (pinfunction "VPWR_P$11") (pintype "bidirectional"))
      (node (ref "U1") (pin "P$31") (pinfunction "VPWR_P$31") (pintype "bidirectional"))
      (node (ref "U1") (pin "P$4") (pinfunction "VPWR_P$4") (pintype "bidirectional"))
      (node (ref "U1") (pin "P$6") (pinfunction "VPWR_P$6") (pintype "bidirectional"))
      (node (ref "U2") (pin "P$11") (pinfunction "VPWR_P$11") (pintype "bidirectional"))
      (node (ref "U2") (pin "P$31") (pinfunction "VPWR_P$31") (pintype "bidirectional"))
      (node (ref "U2") (pin "P$4") (pinfunction "VPWR_P$4") (pintype "bidirectional"))
      (node (ref "U2") (pin "P$6") (pinfunction "VPWR_P$6") (pintype "bidirectional"))
      (node (ref "U3") (pin "P$11") (pinfunction "VPWR_P$11") (pintype "bidirectional"))
      (node (ref "U3") (pin "P$31") (pinfunction "VPWR_P$31") (pintype "bidirectional"))
      (node (ref "U3") (pin "P$4") (pinfunction "VPWR_P$4") (pintype "bidirectional"))
      (node (ref "U3") (pin "P$6") (pinfunction "VPWR_P$6") (pintype "bidirectional"))
      (node (ref "U4") (pin "VIN") (pinfunction "IN_VIN") (pintype "input"))
    )
    (net (code "34") (name "unconnected-(B1-0-Pad32)") (class "Default")
      (node (ref "B1") (pin "32") (pinfunction "0_32") (pintype "bidirectional"))
    )
    (net (code "35") (name "unconnected-(B1-2-Pad31)") (class "Default")
      (node (ref "B1") (pin "31") (pinfunction "2_31") (pintype "bidirectional"))
    )
    (net (code "36") (name "unconnected-(B1-3V3-Pad5)") (class "Default")
      (node (ref "B1") (pin "5") (pinfunction "3V3_5") (pintype "bidirectional"))
    )
    (net (code "37") (name "unconnected-(B1-4-Pad33)") (class "Default")
      (node (ref "B1") (pin "33") (pinfunction "4_33") (pintype "bidirectional"))
    )
    (net (code "38") (name "unconnected-(B1-12-Pad8)") (class "Default")
      (node (ref "B1") (pin "8") (pinfunction "12_8") (pintype "bidirectional"))
    )
    (net (code "39") (name "unconnected-(B1-13-Pad7)") (class "Default")
      (node (ref "B1") (pin "7") (pinfunction "13_7") (pintype "bidirectional"))
    )
    (net (code "40") (name "unconnected-(B1-14-Pad9)") (class "Default")
      (node (ref "B1") (pin "9") (pinfunction "14_9") (pintype "bidirectional"))
    )
    (net (code "41") (name "unconnected-(B1-15-Pad30)") (class "Default")
      (node (ref "B1") (pin "30") (pinfunction "15_30") (pintype "bidirectional"))
    )
    (net (code "42") (name "unconnected-(B1-16-Pad35)") (class "Default")
      (node (ref "B1") (pin "35") (pinfunction "16_35") (pintype "bidirectional"))
    )
    (net (code "43") (name "unconnected-(B1-17-Pad34)") (class "Default")
      (node (ref "B1") (pin "34") (pinfunction "17_34") (pintype "bidirectional"))
    )
    (net (code "44") (name "unconnected-(B1-21-Pad22)") (class "Default")
      (node (ref "B1") (pin "22") (pinfunction "21_22") (pintype "bidirectional"))
    )
    (net (code "45") (name "unconnected-(B1-22-Pad25)") (class "Default")
      (node (ref "B1") (pin "25") (pinfunction "22_25") (pintype "bidirectional"))
    )
    (net (code "46") (name "unconnected-(B1-26-Pad11)") (class "Default")
      (node (ref "B1") (pin "11") (pinfunction "26_11") (pintype "bidirectional"))
    )
    (net (code "47") (name "unconnected-(B1-27-Pad10)") (class "Default")
      (node (ref "B1") (pin "10") (pinfunction "27_10") (pintype "bidirectional"))
    )
    (net (code "48") (name "unconnected-(B1-35-Pad13)") (class "Default")
      (node (ref "B1") (pin "13") (pinfunction "35_13") (pintype "bidirectional"))
    )
    (net (code "49") (name "unconnected-(B1-37-Pad19)") (class "Default")
      (node (ref "B1") (pin "19") (pinfunction "37_19") (pintype "bidirectional"))
    )
    (net (code "50") (name "unconnected-(B1-38-Pad18)") (class "Default")
      (node (ref "B1") (pin "18") (pinfunction "38_18") (pintype "bidirectional"))
    )
    (net (code "51") (name "unconnected-(B1-RX-Pad24)") (class "Default")
      (node (ref "B1") (pin "24") (pinfunction "RX_24") (pintype "bidirectional"))
    )
    (net (code "52") (name "unconnected-(B1-TX-Pad23)") (class "Default")
      (node (ref "B1") (pin "23") (pinfunction "TX_23") (pintype "bidirectional"))
    )
    (net (code "53") (name "unconnected-(B1-VBAT-Pad3)") (class "Default")
      (node (ref "B1") (pin "3") (pinfunction "VBAT_3") (pintype "bidirectional"))
    )
    (net (code "54") (name "unconnected-(B1-VBAT-Pad38)") (class "Default")
      (node (ref "B1") (pin "38") (pinfunction "VBAT_38") (pintype "bidirectional"))
    )
    (net (code "55") (name "unconnected-(B1-VUSB-Pad2)") (class "Default")
      (node (ref "B1") (pin "2") (pinfunction "VUSB_2") (pintype "bidirectional"))
    )
    (net (code "56") (name "unconnected-(B1-~{RST}-Pad6)") (class "Default")
      (node (ref "B1") (pin "6") (pinfunction "~{RST}_6") (pintype "bidirectional"))
    )
    (net (code "57") (name "unconnected-(U1-INV-PadP$7)") (class "Default")
      (node (ref "U1") (pin "P$7") (pinfunction "INV_P$7") (pintype "bidirectional"))
    )
    (net (code "58") (name "unconnected-(U2-INV-PadP$7)") (class "Default")
      (node (ref "U2") (pin "P$7") (pinfunction "INV_P$7") (pintype "bidirectional"))
    )
    (net (code "59") (name "unconnected-(U3-INV-PadP$7)") (class "Default")
      (node (ref "U3") (pin "P$7") (pinfunction "INV_P$7") (pintype "bidirectional"))
    )
  )
)
